# CH32V407RET-R0.net
KiCad netlist of a schematic drawn in Altium Designer
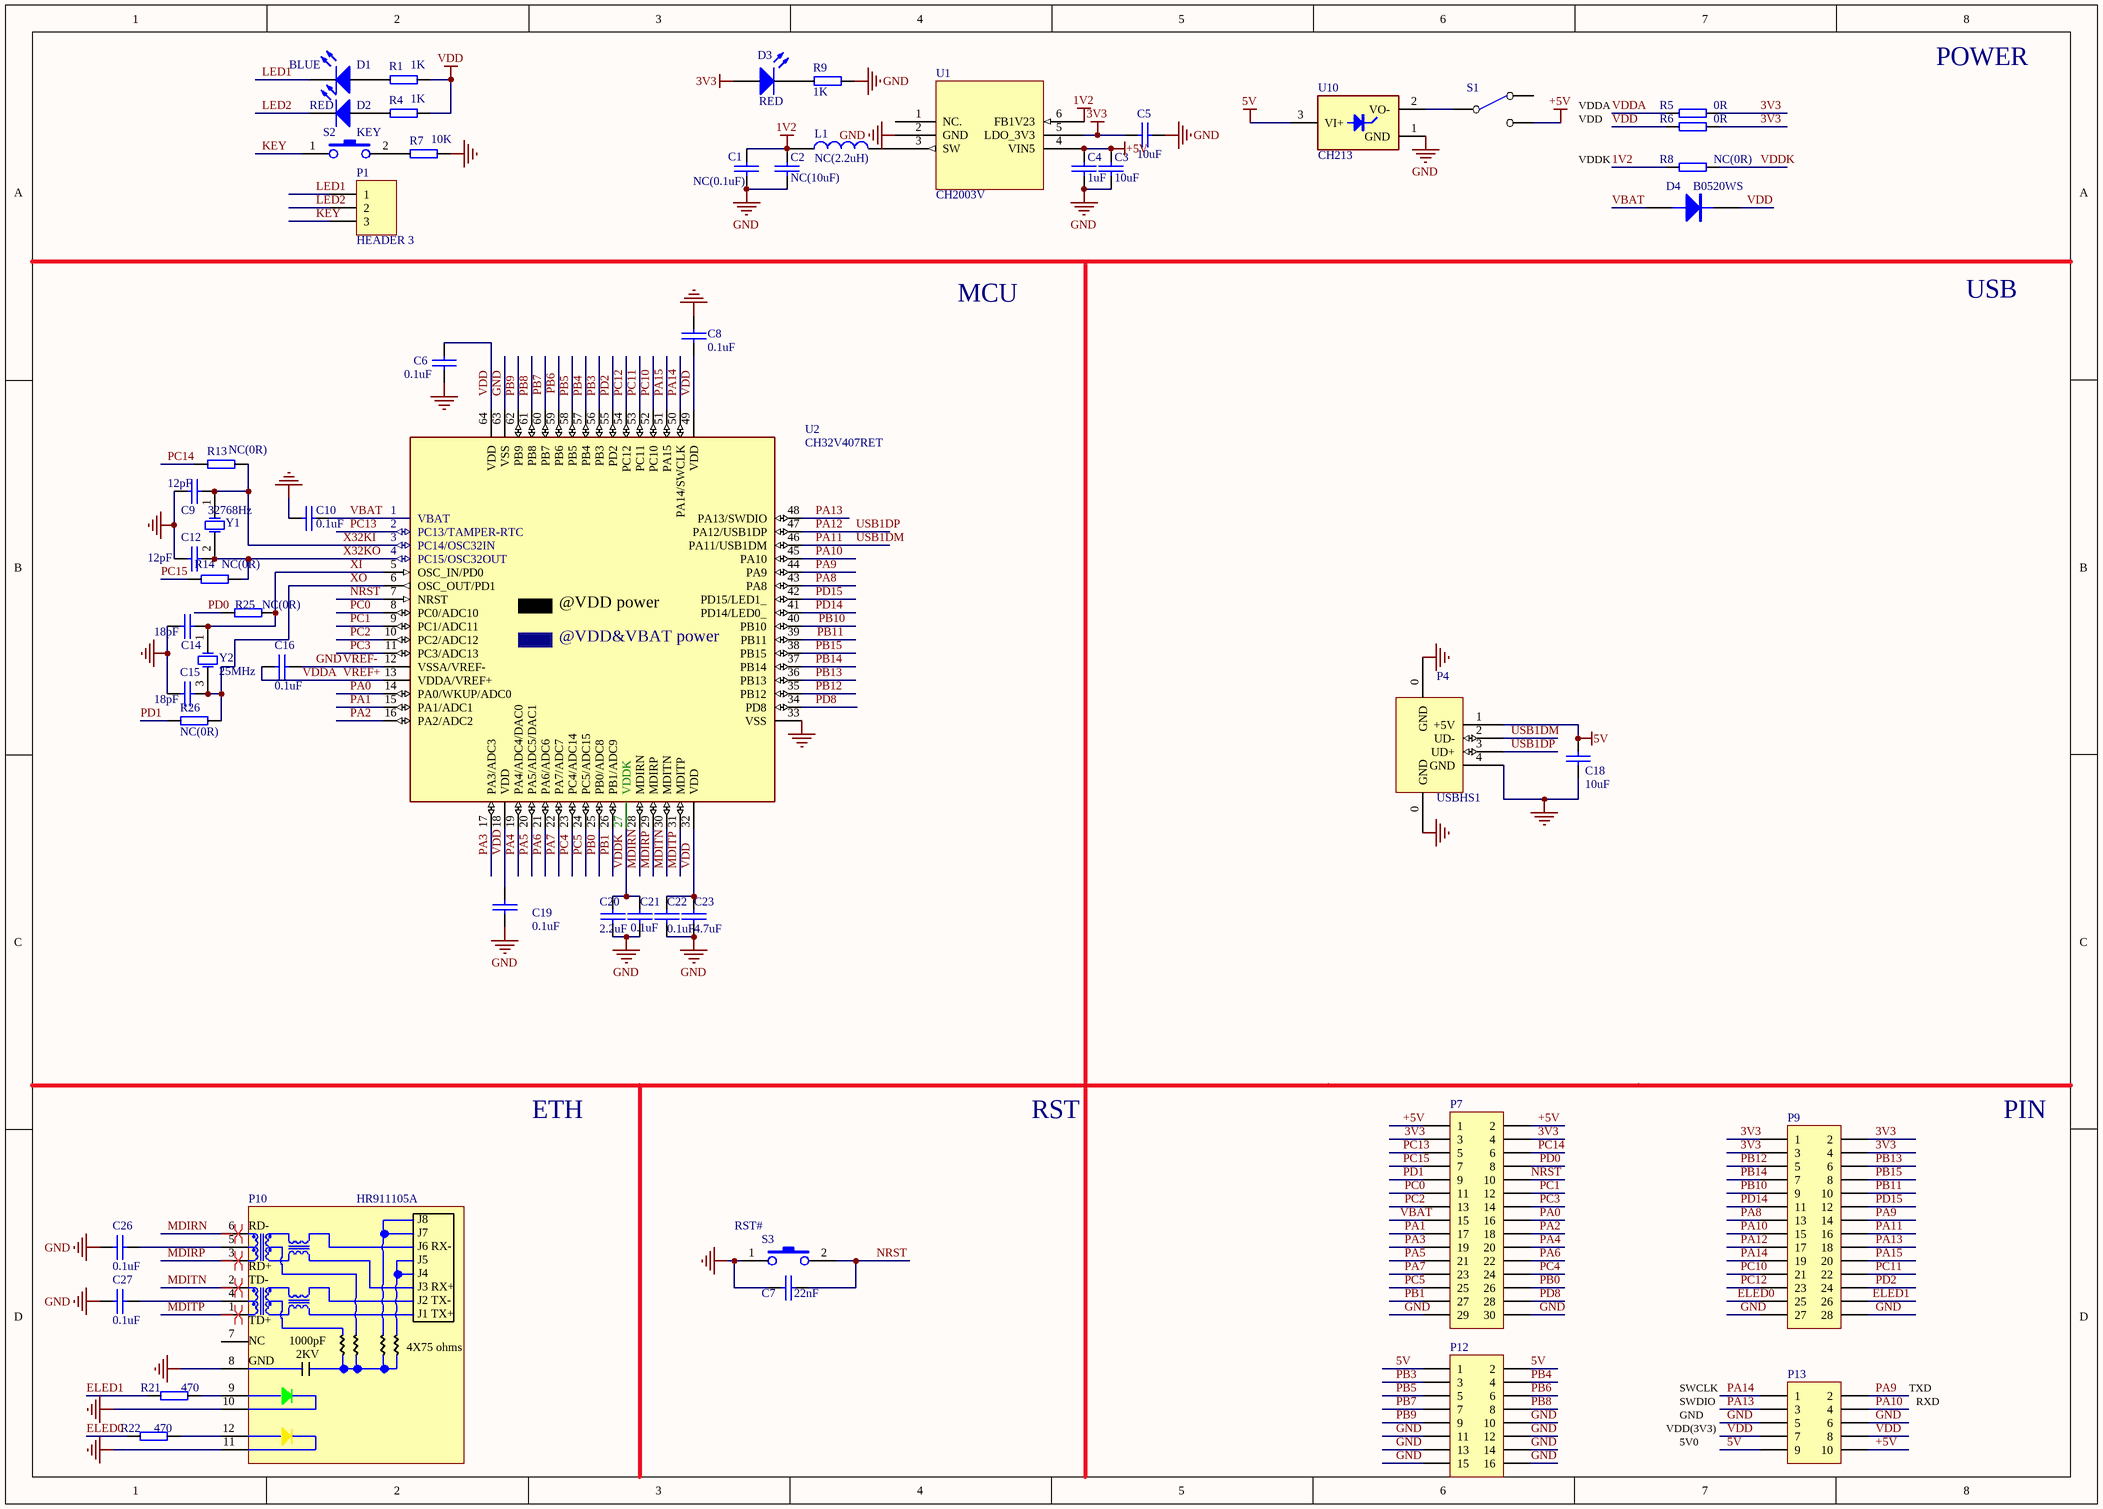
[diagram p0: CH32V407RET-R0.SchDoc]

(export (version "E")
  (design (tool "Eeschema 10.0.6"))
  (components
    (comp (ref "C1")
      (value "NC(0.1uF)")
      (footprint "0402_C")
      (description "Capacitor")
      (libsource (lib "") (part "CAP_1"))
    )
    (comp (ref "C2")
      (value "NC(10uF)")
      (footprint "0603_C")
      (description "Capacitor")
      (libsource (lib "*") (part "CAP"))
    )
    (comp (ref "C3")
      (value "10uF")
      (footprint "0603_C")
      (description "Capacitor")
      (libsource (lib "*") (part "CAP"))
    )
    (comp (ref "C4")
      (value "1uF")
      (footprint "0402_C")
      (description "Capacitor")
      (libsource (lib "") (part "CAP_1"))
    )
    (comp (ref "C5")
      (value "10uF")
      (footprint "0603_C")
      (description "Capacitor")
      (libsource (lib "*") (part "CAP"))
    )
    (comp (ref "C6")
      (value "0.1uF")
      (footprint "0402_C")
      (description "Capacitor")
      (libsource (lib "*") (part "CAP"))
    )
    (comp (ref "C7")
      (value "22nF")
      (footprint "0402_C")
      (description "Capacitor")
      (libsource (lib "") (part "CAP_2"))
    )
    (comp (ref "C8")
      (value "0.1uF")
      (footprint "0402_C")
      (description "Capacitor")
      (libsource (lib "*") (part "CAP"))
    )
    (comp (ref "C9")
      (value "12pF")
      (footprint "0402_C")
      (description "Capacitor")
      (libsource (lib "*") (part "CAP"))
    )
    (comp (ref "C10")
      (value "0.1uF")
      (footprint "0402_C")
      (description "Capacitor")
      (libsource (lib "*") (part "CAP"))
    )
    (comp (ref "C12")
      (value "12pF")
      (footprint "0402_C")
      (description "Capacitor")
      (libsource (lib "*") (part "CAP"))
    )
    (comp (ref "C14")
      (value "18pF")
      (footprint "0402_C")
      (description "Capacitor")
      (libsource (lib "*") (part "CAP"))
    )
    (comp (ref "C15")
      (value "18pF")
      (footprint "0402_C")
      (description "Capacitor")
      (libsource (lib "*") (part "CAP"))
    )
    (comp (ref "C16")
      (value "0.1uF")
      (footprint "0402_C")
      (description "Capacitor")
      (libsource (lib "*") (part "CAP"))
    )
    (comp (ref "C18")
      (value "10uF")
      (footprint "0603_C")
      (description "Capacitor")
      (libsource (lib "") (part "CAP_2"))
    )
    (comp (ref "C19")
      (value "0.1uF")
      (footprint "0402_C")
      (description "Capacitor")
      (libsource (lib "*") (part "CAP"))
    )
    (comp (ref "C20")
      (value "2.2uF")
      (footprint "0402_C")
      (description "Capacitor")
      (libsource (lib "*") (part "CAP"))
    )
    (comp (ref "C21")
      (value "0.1uF")
      (footprint "0402_C")
      (description "Capacitor")
      (libsource (lib "*") (part "CAP"))
    )
    (comp (ref "C22")
      (value "0.1uF")
      (footprint "0402_C")
      (description "Capacitor")
      (libsource (lib "*") (part "CAP"))
    )
    (comp (ref "C23")
      (value "4.7uF")
      (footprint "0402_C")
      (description "Capacitor")
      (libsource (lib "*") (part "CAP"))
    )
    (comp (ref "C26")
      (value "0.1uF")
      (footprint "0402_C")
      (description "Capacitor")
      (libsource (lib "wch_sch_others") (part "CAP"))
    )
    (comp (ref "C27")
      (value "0.1uF")
      (footprint "0402_C")
      (description "Capacitor")
      (libsource (lib "wch_sch_others") (part "CAP"))
    )
    (comp (ref "D1")
      (value "BLUE")
      (footprint "0603+")
      (description "Typical INFRARED GaAs LED")
      (fields (field (name "PUBLISHER") "Altium Limited"))
      (libsource (lib "*") (part "LED0"))
    )
    (comp (ref "D2")
      (value "RED")
      (footprint "0603+")
      (description "Typical INFRARED GaAs LED")
      (fields (field (name "PUBLISHER") "Altium Limited"))
      (libsource (lib "*") (part "LED0"))
    )
    (comp (ref "D3")
      (value "RED")
      (footprint "0603+")
      (description "Typical INFRARED GaAs LED")
      (fields (field (name "PUBLISHER") "Altium Limited"))
      (libsource (lib "*") (part "LED0"))
    )
    (comp (ref "D4")
      (value "B0520WS")
      (footprint "SOD-323")
      (description "Diode")
      (libsource (lib "*") (part "DIODE"))
    )
    (comp (ref "L1") (value "NC(2.2uH)") (footprint "CD32") (libsource (lib "*") (part "INDUCTOR")))
    (comp (ref "P1")
      (value "HEADER 3")
      (footprint "SIP3-2.54MM")
      (description "Header, 3-Pin")
      (libsource (lib "wch_sch_others") (part "HEADER 3"))
    )
    (comp (ref "P4")
      (value "USBHS1")
      (footprint "USBAF")
      (description "USB Port")
      (libsource (lib "*") (part "USB"))
    )
    (comp (ref "P7")
      (value "HEADER 15x2")
      (footprint "MYPCB:IDC30-2.54MM")
      (description "Header, 15-Pin, Dual row")
      (libsource (lib "wch_sch_others") (part "HEADER 15x2"))
    )
    (comp (ref "P9")
      (value "HEADER 14x2")
      (footprint "MYPCB:IDC28-2.54MM")
      (description "Header, 14-Pin, Dual row")
      (libsource (lib "wch_sch_others") (part "HEADER 14x2"))
    )
    (comp (ref "P10") (value "HR911105A") (footprint "HR911105A") (libsource (lib "*") (part "HR911105A")))
    (comp (ref "P12")
      (value "Ppin")
      (footprint "IDC16-2.54mm")
      (description "Header, 8-Pin, Dual row, Right Angle")
      (fields (field (name "PUBLISHER") "Altium Limited"))
      (libsource (lib "Miscellaneous Connectors") (part "Header 8X2H"))
    )
    (comp (ref "P13")
      (value "LINK")
      (footprint "IDC10-2.54mm")
      (description "Header, 5-Pin, Dual row, Right Angle")
      (fields (field (name "PUBLISHER") "Altium Limited"))
      (libsource (lib "Miscellaneous Connectors") (part "Header 5X2H"))
    )
    (comp (ref "R1") (value "1K") (footprint "0402") (libsource (lib "wch_sch_others") (part "RES")))
    (comp (ref "R4") (value "1K") (footprint "0402") (libsource (lib "wch_sch_others") (part "RES")))
    (comp (ref "R5") (value "0R") (footprint "0402") (libsource (lib "*") (part "R")))
    (comp (ref "R6") (value "0R") (footprint "0402") (libsource (lib "*") (part "R")))
    (comp (ref "R7") (value "10K") (footprint "0402") (libsource (lib "wch_sch_others") (part "RES")))
    (comp (ref "R8") (value "NC(0R)") (footprint "0402") (libsource (lib "*") (part "R")))
    (comp (ref "R9") (value "1K") (footprint "0402") (libsource (lib "wch_sch_others") (part "RES")))
    (comp (ref "R13") (value "NC(0R)") (footprint "0402") (libsource (lib "wch_sch_others") (part "RES")))
    (comp (ref "R14") (value "NC(0R)") (footprint "0402") (libsource (lib "wch_sch_others") (part "RES")))
    (comp (ref "R21") (value "470") (footprint "0402") (libsource (lib "wch_sch_others") (part "RES")))
    (comp (ref "R22") (value "470") (footprint "0402") (libsource (lib "wch_sch_others") (part "RES")))
    (comp (ref "R25") (value "NC(0R)") (footprint "0402") (libsource (lib "wch_sch_others") (part "RES")))
    (comp (ref "R26") (value "NC(0R)") (footprint "0402") (libsource (lib "wch_sch_others") (part "RES")))
    (comp (ref "S1") (value "SW SPDT") (footprint "SW1") (libsource (lib "*") (part "SW SPDT")))
    (comp (ref "S2")
      (value "KEY")
      (footprint "SMD_6.1x3.65x2.5mm-KEY")
      (libsource (lib "wch_sch_others") (part "KEY1"))
    )
    (comp (ref "S3")
      (value "RST#")
      (footprint "SMD_6.1x3.65x2.5mm-KEY")
      (libsource (lib "wch_sch_others") (part "KEY1"))
    )
    (comp (ref "U1")
      (value "CH2003V")
      (footprint "SOT-23-6")
      (description "Step-Down DC-DC Converter, 5V input, 1.23V * 800mA output, with LDO 3.3V * 200mA")
      (libsource (lib "CHXXX") (part "CH2003V"))
    )
    (comp (ref "U2")
      (value "CH32V407RET")
      (footprint "LQFP64_7X7")
      (description "RISC-V FPU HD-MCU, 175MHz, USB_480M, 100M Ethernet & Phy, CAN, ADC, DAC")
      (libsource (lib "DHXXXSCH") (part "CH32V407RET"))
    )
    (comp (ref "U10")
      (value "CH213")
      (footprint "SOT-23-3")
      (description "Ideal Diode 5V*1A")
      (libsource (lib "CHXXX") (part "CH213E"))
    )
    (comp (ref "Y1")
      (value "32768Hz")
      (footprint "FC-135")
      (description "Crystal Oscillator")
      (fields (field (name "PUBLISHER") "Altium Limited"))
      (libsource (lib "*") (part "XTAL"))
    )
    (comp (ref "Y2")
      (value "25MHz")
      (footprint "XT3225")
      (description "Crystal Oscillator")
      (fields (field (name "PUBLISHER") "Altium Limited"))
      (libsource (lib "") (part "XTAL_1"))
    )
  )
  (nets
    (net (code "1") (name "+5V") (class "Default")
      (node (ref "C3") (pin "2") (pinfunction "2_2") (pintype "passive"))
      (node (ref "C4") (pin "2") (pinfunction "2_2") (pintype "passive"))
      (node (ref "P13") (pin "10") (pinfunction "10_10") (pintype "passive"))
      (node (ref "P7") (pin "1") (pinfunction "1_1") (pintype "passive"))
      (node (ref "P7") (pin "2") (pinfunction "2_2") (pintype "passive"))
      (node (ref "S1") (pin "2") (pinfunction "NC_2") (pintype "passive"))
      (node (ref "U1") (pin "4") (pinfunction "VIN5_4") (pintype "power_in"))
    )
    (net (code "3") (name "/ELED0") (class "Default")
      (node (ref "P9") (pin "25") (pinfunction "25_25") (pintype "passive"))
      (node (ref "R22") (pin "1") (pintype "passive"))
    )
    (net (code "4") (name "/ELED1") (class "Default")
      (node (ref "P9") (pin "26") (pinfunction "26_26") (pintype "passive"))
      (node (ref "R21") (pin "1") (pintype "passive"))
    )
    (net (code "5") (name "/KEY") (class "Default")
      (node (ref "P1") (pin "3") (pinfunction "3_3") (pintype "passive"))
      (node (ref "S2") (pin "1") (pinfunction "1_1") (pintype "passive"))
    )
    (net (code "6") (name "/LED1") (class "Default")
      (node (ref "D1") (pin "2") (pinfunction "K_2") (pintype "passive"))
      (node (ref "P1") (pin "1") (pinfunction "1_1") (pintype "passive"))
    )
    (net (code "7") (name "/LED2") (class "Default")
      (node (ref "D2") (pin "2") (pinfunction "K_2") (pintype "passive"))
      (node (ref "P1") (pin "2") (pinfunction "2_2") (pintype "passive"))
    )
    (net (code "8") (name "/MDIRN") (class "Default")
      (node (ref "P10") (pin "6") (pintype "passive"))
      (node (ref "U2") (pin "28") (pinfunction "MDIRN_28") (pintype "bidirectional"))
    )
    (net (code "9") (name "/MDIRP") (class "Default")
      (node (ref "P10") (pin "3") (pintype "passive"))
      (node (ref "U2") (pin "29") (pinfunction "MDIRP_29") (pintype "bidirectional"))
    )
    (net (code "10") (name "/MDITN") (class "Default")
      (node (ref "P10") (pin "2") (pintype "passive"))
      (node (ref "U2") (pin "30") (pinfunction "MDITN_30") (pintype "bidirectional"))
    )
    (net (code "11") (name "/MDITP") (class "Default")
      (node (ref "P10") (pin "1") (pintype "passive"))
      (node (ref "U2") (pin "31") (pinfunction "MDITP_31") (pintype "bidirectional"))
    )
    (net (code "12") (name "/NRST") (class "Default")
      (node (ref "C7") (pin "2") (pinfunction "2_2") (pintype "passive"))
      (node (ref "P7") (pin "10") (pinfunction "10_10") (pintype "passive"))
      (node (ref "S3") (pin "2") (pinfunction "2_2") (pintype "passive"))
      (node (ref "U2") (pin "7") (pinfunction "NRST_7") (pintype "input"))
    )
    (net (code "13") (name "/PA0") (class "Default")
      (node (ref "P7") (pin "16") (pinfunction "16_16") (pintype "passive"))
      (node (ref "U2") (pin "14") (pinfunction "PA0/WKUP/ADC0_14") (pintype "bidirectional"))
    )
    (net (code "14") (name "/PA1") (class "Default")
      (node (ref "P7") (pin "17") (pinfunction "17_17") (pintype "passive"))
      (node (ref "U2") (pin "15") (pinfunction "PA1/ADC1_15") (pintype "bidirectional"))
    )
    (net (code "15") (name "/PA2") (class "Default")
      (node (ref "P7") (pin "18") (pinfunction "18_18") (pintype "passive"))
      (node (ref "U2") (pin "16") (pinfunction "PA2/ADC2_16") (pintype "bidirectional"))
    )
    (net (code "16") (name "/PA3") (class "Default")
      (node (ref "P7") (pin "19") (pinfunction "19_19") (pintype "passive"))
      (node (ref "U2") (pin "17") (pinfunction "PA3/ADC3_17") (pintype "bidirectional"))
    )
    (net (code "17") (name "/PA4") (class "Default")
      (node (ref "P7") (pin "20") (pinfunction "20_20") (pintype "passive"))
      (node (ref "U2") (pin "19") (pinfunction "PA4/ADC4/DAC0_19") (pintype "bidirectional"))
    )
    (net (code "18") (name "/PA5") (class "Default")
      (node (ref "P7") (pin "21") (pinfunction "21_21") (pintype "passive"))
      (node (ref "U2") (pin "20") (pinfunction "PA5/ADC5/DAC1_20") (pintype "bidirectional"))
    )
    (net (code "19") (name "/PA6") (class "Default")
      (node (ref "P7") (pin "22") (pinfunction "22_22") (pintype "passive"))
      (node (ref "U2") (pin "21") (pinfunction "PA6/ADC6_21") (pintype "bidirectional"))
    )
    (net (code "20") (name "/PA7") (class "Default")
      (node (ref "P7") (pin "23") (pinfunction "23_23") (pintype "passive"))
      (node (ref "U2") (pin "22") (pinfunction "PA7/ADC7_22") (pintype "bidirectional"))
    )
    (net (code "21") (name "/PA8") (class "Default")
      (node (ref "P9") (pin "13") (pinfunction "13_13") (pintype "passive"))
      (node (ref "U2") (pin "43") (pinfunction "PA8_43") (pintype "bidirectional"))
    )
    (net (code "22") (name "/PA9") (class "Default")
      (node (ref "P13") (pin "2") (pinfunction "2_2") (pintype "passive"))
      (node (ref "P9") (pin "14") (pinfunction "14_14") (pintype "passive"))
      (node (ref "U2") (pin "44") (pinfunction "PA9_44") (pintype "bidirectional"))
    )
    (net (code "23") (name "/PA10") (class "Default")
      (node (ref "P13") (pin "4") (pinfunction "4_4") (pintype "passive"))
      (node (ref "P9") (pin "15") (pinfunction "15_15") (pintype "passive"))
      (node (ref "U2") (pin "45") (pinfunction "PA10_45") (pintype "bidirectional"))
    )
    (net (code "24") (name "/PA11") (class "Default")
      (node (ref "P4") (pin "2") (pinfunction "UD-_2") (pintype "bidirectional"))
      (node (ref "P9") (pin "16") (pinfunction "16_16") (pintype "passive"))
      (node (ref "U2") (pin "46") (pinfunction "PA11/USB1DM_46") (pintype "bidirectional"))
    )
    (net (code "25") (name "/PA12") (class "Default")
      (node (ref "P4") (pin "3") (pinfunction "UD+_3") (pintype "bidirectional"))
      (node (ref "P9") (pin "17") (pinfunction "17_17") (pintype "passive"))
      (node (ref "U2") (pin "47") (pinfunction "PA12/USB1DP_47") (pintype "bidirectional"))
    )
    (net (code "26") (name "/PA13") (class "Default")
      (node (ref "P13") (pin "3") (pinfunction "3_3") (pintype "passive"))
      (node (ref "P9") (pin "18") (pinfunction "18_18") (pintype "passive"))
      (node (ref "U2") (pin "48") (pinfunction "PA13/SWDIO_48") (pintype "bidirectional"))
    )
    (net (code "27") (name "/PA14") (class "Default")
      (node (ref "P13") (pin "1") (pinfunction "1_1") (pintype "passive"))
      (node (ref "P9") (pin "19") (pinfunction "19_19") (pintype "passive"))
      (node (ref "U2") (pin "50") (pinfunction "PA14/SWCLK_50") (pintype "bidirectional"))
    )
    (net (code "28") (name "/PA15") (class "Default")
      (node (ref "P9") (pin "20") (pinfunction "20_20") (pintype "passive"))
      (node (ref "U2") (pin "51") (pinfunction "PA15_51") (pintype "bidirectional"))
    )
    (net (code "29") (name "/PB0") (class "Default")
      (node (ref "P7") (pin "26") (pinfunction "26_26") (pintype "passive"))
      (node (ref "U2") (pin "25") (pinfunction "PB0/ADC8_25") (pintype "bidirectional"))
    )
    (net (code "30") (name "/PB1") (class "Default")
      (node (ref "P7") (pin "27") (pinfunction "27_27") (pintype "passive"))
      (node (ref "U2") (pin "26") (pinfunction "PB1/ADC9_26") (pintype "bidirectional"))
    )
    (net (code "31") (name "/PB3") (class "Default")
      (node (ref "P12") (pin "3") (pinfunction "3_3") (pintype "passive"))
      (node (ref "U2") (pin "56") (pinfunction "PB3_56") (pintype "bidirectional"))
    )
    (net (code "32") (name "/PB4") (class "Default")
      (node (ref "P12") (pin "4") (pinfunction "4_4") (pintype "passive"))
      (node (ref "U2") (pin "57") (pinfunction "PB4_57") (pintype "bidirectional"))
    )
    (net (code "33") (name "/PB5") (class "Default")
      (node (ref "P12") (pin "5") (pinfunction "5_5") (pintype "passive"))
      (node (ref "U2") (pin "58") (pinfunction "PB5_58") (pintype "bidirectional"))
    )
    (net (code "34") (name "/PB6") (class "Default")
      (node (ref "P12") (pin "6") (pinfunction "6_6") (pintype "passive"))
      (node (ref "U2") (pin "59") (pinfunction "PB6_59") (pintype "bidirectional"))
    )
    (net (code "35") (name "/PB7") (class "Default")
      (node (ref "P12") (pin "7") (pinfunction "7_7") (pintype "passive"))
      (node (ref "U2") (pin "60") (pinfunction "PB7_60") (pintype "bidirectional"))
    )
    (net (code "36") (name "/PB8") (class "Default")
      (node (ref "P12") (pin "8") (pinfunction "8_8") (pintype "passive"))
      (node (ref "U2") (pin "61") (pinfunction "PB8_61") (pintype "bidirectional"))
    )
    (net (code "37") (name "/PB9") (class "Default")
      (node (ref "P12") (pin "9") (pinfunction "9_9") (pintype "passive"))
      (node (ref "U2") (pin "62") (pinfunction "PB9_62") (pintype "bidirectional"))
    )
    (net (code "38") (name "/PB10") (class "Default")
      (node (ref "P9") (pin "9") (pinfunction "9_9") (pintype "passive"))
      (node (ref "U2") (pin "40") (pinfunction "PB10_40") (pintype "bidirectional"))
    )
    (net (code "39") (name "/PB11") (class "Default")
      (node (ref "P9") (pin "10") (pinfunction "10_10") (pintype "passive"))
      (node (ref "U2") (pin "39") (pinfunction "PB11_39") (pintype "bidirectional"))
    )
    (net (code "40") (name "/PB12") (class "Default")
      (node (ref "P9") (pin "5") (pinfunction "5_5") (pintype "passive"))
      (node (ref "U2") (pin "35") (pinfunction "PB12_35") (pintype "bidirectional"))
    )
    (net (code "41") (name "/PB13") (class "Default")
      (node (ref "P9") (pin "6") (pinfunction "6_6") (pintype "passive"))
      (node (ref "U2") (pin "36") (pinfunction "PB13_36") (pintype "bidirectional"))
    )
    (net (code "42") (name "/PB14") (class "Default")
      (node (ref "P9") (pin "7") (pinfunction "7_7") (pintype "passive"))
      (node (ref "U2") (pin "37") (pinfunction "PB14_37") (pintype "bidirectional"))
    )
    (net (code "43") (name "/PB15") (class "Default")
      (node (ref "P9") (pin "8") (pinfunction "8_8") (pintype "passive"))
      (node (ref "U2") (pin "38") (pinfunction "PB15_38") (pintype "bidirectional"))
    )
    (net (code "44") (name "/PC0") (class "Default")
      (node (ref "P7") (pin "11") (pinfunction "11_11") (pintype "passive"))
      (node (ref "U2") (pin "8") (pinfunction "PC0/ADC10_8") (pintype "bidirectional"))
    )
    (net (code "45") (name "/PC1") (class "Default")
      (node (ref "P7") (pin "12") (pinfunction "12_12") (pintype "passive"))
      (node (ref "U2") (pin "9") (pinfunction "PC1/ADC11_9") (pintype "bidirectional"))
    )
    (net (code "46") (name "/PC2") (class "Default")
      (node (ref "P7") (pin "13") (pinfunction "13_13") (pintype "passive"))
      (node (ref "U2") (pin "10") (pinfunction "PC2/ADC12_10") (pintype "bidirectional"))
    )
    (net (code "47") (name "/PC3") (class "Default")
      (node (ref "P7") (pin "14") (pinfunction "14_14") (pintype "passive"))
      (node (ref "U2") (pin "11") (pinfunction "PC3/ADC13_11") (pintype "bidirectional"))
    )
    (net (code "48") (name "/PC4") (class "Default")
      (node (ref "P7") (pin "24") (pinfunction "24_24") (pintype "passive"))
      (node (ref "U2") (pin "23") (pinfunction "PC4/ADC14_23") (pintype "bidirectional"))
    )
    (net (code "49") (name "/PC5") (class "Default")
      (node (ref "P7") (pin "25") (pinfunction "25_25") (pintype "passive"))
      (node (ref "U2") (pin "24") (pinfunction "PC5/ADC15_24") (pintype "bidirectional"))
    )
    (net (code "50") (name "/PC10") (class "Default")
      (node (ref "P9") (pin "21") (pinfunction "21_21") (pintype "passive"))
      (node (ref "U2") (pin "52") (pinfunction "PC10_52") (pintype "bidirectional"))
    )
    (net (code "51") (name "/PC11") (class "Default")
      (node (ref "P9") (pin "22") (pinfunction "22_22") (pintype "passive"))
      (node (ref "U2") (pin "53") (pinfunction "PC11_53") (pintype "bidirectional"))
    )
    (net (code "52") (name "/PC12") (class "Default")
      (node (ref "P9") (pin "23") (pinfunction "23_23") (pintype "passive"))
      (node (ref "U2") (pin "54") (pinfunction "PC12_54") (pintype "bidirectional"))
    )
    (net (code "53") (name "/PC13") (class "Default")
      (node (ref "P7") (pin "5") (pinfunction "5_5") (pintype "passive"))
      (node (ref "U2") (pin "2") (pinfunction "PC13/TAMPER-RTC_2") (pintype "bidirectional"))
    )
    (net (code "54") (name "/PC14") (class "Default")
      (node (ref "P7") (pin "6") (pinfunction "6_6") (pintype "passive"))
      (node (ref "R13") (pin "1") (pintype "passive"))
    )
    (net (code "55") (name "/PC15") (class "Default")
      (node (ref "P7") (pin "7") (pinfunction "7_7") (pintype "passive"))
      (node (ref "R14") (pin "1") (pintype "passive"))
    )
    (net (code "56") (name "/PD0") (class "Default")
      (node (ref "P7") (pin "8") (pinfunction "8_8") (pintype "passive"))
      (node (ref "R25") (pin "1") (pintype "passive"))
    )
    (net (code "57") (name "/PD1") (class "Default")
      (node (ref "P7") (pin "9") (pinfunction "9_9") (pintype "passive"))
      (node (ref "R26") (pin "2") (pintype "passive"))
    )
    (net (code "58") (name "/PD2") (class "Default")
      (node (ref "P9") (pin "24") (pinfunction "24_24") (pintype "passive"))
      (node (ref "U2") (pin "55") (pinfunction "PD2_55") (pintype "bidirectional"))
    )
    (net (code "59") (name "/PD8") (class "Default")
      (node (ref "P7") (pin "28") (pinfunction "28_28") (pintype "passive"))
      (node (ref "U2") (pin "34") (pinfunction "PD8_34") (pintype "bidirectional"))
    )
    (net (code "60") (name "/PD14") (class "Default")
      (node (ref "P9") (pin "11") (pinfunction "11_11") (pintype "passive"))
      (node (ref "U2") (pin "41") (pinfunction "PD14/LED0__41") (pintype "bidirectional"))
    )
    (net (code "61") (name "/PD15") (class "Default")
      (node (ref "P9") (pin "12") (pinfunction "12_12") (pintype "passive"))
      (node (ref "U2") (pin "42") (pinfunction "PD15/LED1__42") (pintype "bidirectional"))
    )
    (net (code "62") (name "/VBAT") (class "Default")
      (node (ref "C10") (pin "2") (pinfunction "2_2") (pintype "passive"))
      (node (ref "D4") (pin "1") (pinfunction "A_1") (pintype "passive"))
      (node (ref "P7") (pin "15") (pinfunction "15_15") (pintype "passive"))
      (node (ref "U2") (pin "1") (pinfunction "VBAT_1") (pintype "power_in"))
    )
    (net (code "63") (name "/VDDA") (class "Default")
      (node (ref "C16") (pin "1") (pinfunction "1_1") (pintype "passive"))
      (node (ref "R5") (pin "2") (pinfunction "2_2") (pintype "passive"))
      (node (ref "U2") (pin "13") (pinfunction "VDDA/VREF+_13") (pintype "power_in"))
    )
    (net (code "64") (name "/VDDK") (class "Default")
      (node (ref "C20") (pin "2") (pinfunction "2_2") (pintype "passive"))
      (node (ref "C21") (pin "2") (pinfunction "2_2") (pintype "passive"))
      (node (ref "R8") (pin "1") (pinfunction "1_1") (pintype "passive"))
      (node (ref "U2") (pin "27") (pinfunction "VDDK_27") (pintype "power_in"))
    )
    (net (code "65") (name "/X32KI") (class "Default")
      (node (ref "C9") (pin "2") (pinfunction "2_2") (pintype "passive"))
      (node (ref "R13") (pin "2") (pintype "passive"))
      (node (ref "U2") (pin "3") (pinfunction "PC14/OSC32IN_3") (pintype "bidirectional"))
      (node (ref "Y1") (pin "1") (pinfunction "OSC1_1") (pintype "passive"))
    )
    (net (code "66") (name "/X32KO") (class "Default")
      (node (ref "C12") (pin "2") (pinfunction "2_2") (pintype "passive"))
      (node (ref "R14") (pin "2") (pintype "passive"))
      (node (ref "U2") (pin "4") (pinfunction "PC15/OSC32OUT_4") (pintype "bidirectional"))
      (node (ref "Y1") (pin "2") (pinfunction "OSC2_2") (pintype "passive"))
    )
    (net (code "67") (name "/XI") (class "Default")
      (node (ref "C14") (pin "2") (pinfunction "2_2") (pintype "passive"))
      (node (ref "R25") (pin "2") (pintype "passive"))
      (node (ref "U2") (pin "5") (pinfunction "OSC_IN/PD0_5") (pintype "input"))
      (node (ref "Y2") (pin "1") (pinfunction "OSC1_1") (pintype "passive"))
    )
    (net (code "68") (name "/XO") (class "Default")
      (node (ref "C15") (pin "2") (pinfunction "2_2") (pintype "passive"))
      (node (ref "R26") (pin "1") (pintype "passive"))
      (node (ref "U2") (pin "6") (pinfunction "OSC_OUT/PD1_6") (pintype "output"))
      (node (ref "Y2") (pin "3") (pinfunction "OSC2_3") (pintype "passive"))
    )
    (net (code "69") (name "1V2") (class "Default")
      (node (ref "C1") (pin "2") (pinfunction "2_2") (pintype "passive"))
      (node (ref "C2") (pin "2") (pinfunction "2_2") (pintype "passive"))
      (node (ref "L1") (pin "2") (pinfunction "2_2") (pintype "passive"))
      (node (ref "R8") (pin "2") (pinfunction "2_2") (pintype "passive"))
      (node (ref "U1") (pin "6") (pinfunction "FB1V23_6") (pintype "input"))
    )
    (net (code "70") (name "3V3") (class "Default")
      (node (ref "C5") (pin "2") (pinfunction "2_2") (pintype "passive"))
      (node (ref "D3") (pin "1") (pinfunction "A_1") (pintype "passive"))
      (node (ref "P7") (pin "3") (pinfunction "3_3") (pintype "passive"))
      (node (ref "P7") (pin "4") (pinfunction "4_4") (pintype "passive"))
      (node (ref "P9") (pin "1") (pinfunction "1_1") (pintype "passive"))
      (node (ref "P9") (pin "2") (pinfunction "2_2") (pintype "passive"))
      (node (ref "P9") (pin "3") (pinfunction "3_3") (pintype "passive"))
      (node (ref "P9") (pin "4") (pinfunction "4_4") (pintype "passive"))
      (node (ref "R5") (pin "1") (pinfunction "1_1") (pintype "passive"))
      (node (ref "R6") (pin "1") (pinfunction "1_1") (pintype "passive"))
      (node (ref "U1") (pin "5") (pinfunction "LDO_3V3_5") (pintype "power_in"))
    )
    (net (code "71") (name "5V") (class "Default")
      (node (ref "C18") (pin "1") (pinfunction "1_1") (pintype "passive"))
      (node (ref "P12") (pin "1") (pinfunction "1_1") (pintype "passive"))
      (node (ref "P12") (pin "2") (pinfunction "2_2") (pintype "passive"))
      (node (ref "P13") (pin "9") (pinfunction "9_9") (pintype "passive"))
      (node (ref "P4") (pin "1") (pinfunction "+5V_1") (pintype "power_in"))
      (node (ref "U10") (pin "3") (pinfunction "VI+_3") (pintype "power_in"))
    )
    (net (code "72") (name "GND") (class "Default")
      (node (ref "C1") (pin "1") (pinfunction "1_1") (pintype "passive"))
      (node (ref "C10") (pin "1") (pinfunction "1_1") (pintype "passive"))
      (node (ref "C12") (pin "1") (pinfunction "1_1") (pintype "passive"))
      (node (ref "C14") (pin "1") (pinfunction "1_1") (pintype "passive"))
      (node (ref "C15") (pin "1") (pinfunction "1_1") (pintype "passive"))
      (node (ref "C16") (pin "2") (pinfunction "2_2") (pintype "passive"))
      (node (ref "C18") (pin "2") (pinfunction "2_2") (pintype "passive"))
      (node (ref "C19") (pin "1") (pinfunction "1_1") (pintype "passive"))
      (node (ref "C2") (pin "1") (pinfunction "1_1") (pintype "passive"))
      (node (ref "C20") (pin "1") (pinfunction "1_1") (pintype "passive"))
      (node (ref "C21") (pin "1") (pinfunction "1_1") (pintype "passive"))
      (node (ref "C22") (pin "1") (pinfunction "1_1") (pintype "passive"))
      (node (ref "C23") (pin "1") (pinfunction "1_1") (pintype "passive"))
      (node (ref "C26") (pin "1") (pinfunction "1_1") (pintype "passive"))
      (node (ref "C27") (pin "1") (pinfunction "1_1") (pintype "passive"))
      (node (ref "C3") (pin "1") (pinfunction "1_1") (pintype "passive"))
      (node (ref "C4") (pin "1") (pinfunction "1_1") (pintype "passive"))
      (node (ref "C5") (pin "1") (pinfunction "1_1") (pintype "passive"))
      (node (ref "C6") (pin "1") (pinfunction "1_1") (pintype "passive"))
      (node (ref "C7") (pin "1") (pinfunction "1_1") (pintype "passive"))
      (node (ref "C8") (pin "2") (pinfunction "2_2") (pintype "passive"))
      (node (ref "C9") (pin "1") (pinfunction "1_1") (pintype "passive"))
      (node (ref "P10") (pin "10") (pintype "passive"))
      (node (ref "P10") (pin "11") (pintype "passive"))
      (node (ref "P10") (pin "8") (pintype "passive"))
      (node (ref "P12") (pin "10") (pinfunction "10_10") (pintype "passive"))
      (node (ref "P12") (pin "11") (pinfunction "11_11") (pintype "passive"))
      (node (ref "P12") (pin "12") (pinfunction "12_12") (pintype "passive"))
      (node (ref "P12") (pin "13") (pinfunction "13_13") (pintype "passive"))
      (node (ref "P12") (pin "14") (pinfunction "14_14") (pintype "passive"))
      (node (ref "P12") (pin "15") (pinfunction "15_15") (pintype "passive"))
      (node (ref "P12") (pin "16") (pinfunction "16_16") (pintype "passive"))
      (node (ref "P13") (pin "5") (pinfunction "5_5") (pintype "passive"))
      (node (ref "P13") (pin "6") (pinfunction "6_6") (pintype "passive"))
      (node (ref "P4") (pin "0") (pinfunction "GND_0") (pintype "power_in"))
      (node (ref "P4") (pin "4") (pinfunction "GND_4") (pintype "power_in"))
      (node (ref "P7") (pin "29") (pinfunction "29_29") (pintype "passive"))
      (node (ref "P7") (pin "30") (pinfunction "30_30") (pintype "passive"))
      (node (ref "P9") (pin "27") (pinfunction "27_27") (pintype "passive"))
      (node (ref "P9") (pin "28") (pinfunction "28_28") (pintype "passive"))
      (node (ref "R7") (pin "1") (pintype "passive"))
      (node (ref "R9") (pin "2") (pintype "passive"))
      (node (ref "S3") (pin "1") (pinfunction "1_1") (pintype "passive"))
      (node (ref "U1") (pin "2") (pinfunction "GND_2") (pintype "power_in"))
      (node (ref "U10") (pin "1") (pinfunction "GND_1") (pintype "power_in"))
      (node (ref "U2") (pin "12") (pinfunction "VSSA/VREF-_12") (pintype "power_in"))
      (node (ref "U2") (pin "33") (pinfunction "VSS_33") (pintype "power_in"))
      (node (ref "U2") (pin "63") (pinfunction "VSS_63") (pintype "power_in"))
    )
    (net (code "73") (name "Net-(C26-Pad2)") (class "Default")
      (node (ref "C26") (pin "2") (pinfunction "2_2") (pintype "passive"))
      (node (ref "P10") (pin "5") (pintype "passive"))
    )
    (net (code "74") (name "Net-(C27-Pad2)") (class "Default")
      (node (ref "C27") (pin "2") (pinfunction "2_2") (pintype "passive"))
      (node (ref "P10") (pin "4") (pintype "passive"))
    )
    (net (code "75") (name "Net-(D1-A)") (class "Default")
      (node (ref "D1") (pin "1") (pinfunction "A_1") (pintype "passive"))
      (node (ref "R1") (pin "2") (pintype "passive"))
    )
    (net (code "76") (name "Net-(D2-A)") (class "Default")
      (node (ref "D2") (pin "1") (pinfunction "A_1") (pintype "passive"))
      (node (ref "R4") (pin "2") (pintype "passive"))
    )
    (net (code "77") (name "Net-(D3-K)") (class "Default")
      (node (ref "D3") (pin "2") (pinfunction "K_2") (pintype "passive"))
      (node (ref "R9") (pin "1") (pintype "passive"))
    )
    (net (code "78") (name "Net-(P10-Pad9)") (class "Default")
      (node (ref "P10") (pin "9") (pintype "passive"))
      (node (ref "R21") (pin "2") (pintype "passive"))
    )
    (net (code "79") (name "Net-(P10-Pad12)") (class "Default")
      (node (ref "P10") (pin "12") (pintype "passive"))
      (node (ref "R22") (pin "2") (pintype "passive"))
    )
    (net (code "80") (name "Net-(R7-Pad2)") (class "Default")
      (node (ref "R7") (pin "2") (pintype "passive"))
      (node (ref "S2") (pin "2") (pinfunction "2_2") (pintype "passive"))
    )
    (net (code "81") (name "Net-(S1-COMMON)") (class "Default")
      (node (ref "S1") (pin "1") (pinfunction "COMMON_1") (pintype "passive"))
      (node (ref "U10") (pin "2") (pinfunction "VO-_2") (pintype "power_in"))
    )
    (net (code "82") (name "Net-(U1-SW)") (class "Default")
      (node (ref "L1") (pin "1") (pinfunction "1_1") (pintype "passive"))
      (node (ref "U1") (pin "3") (pinfunction "SW_3") (pintype "output"))
    )
    (net (code "83") (name "VDD") (class "Default")
      (node (ref "C19") (pin "2") (pinfunction "2_2") (pintype "passive"))
      (node (ref "C22") (pin "2") (pinfunction "2_2") (pintype "passive"))
      (node (ref "C23") (pin "2") (pinfunction "2_2") (pintype "passive"))
      (node (ref "C6") (pin "2") (pinfunction "2_2") (pintype "passive"))
      (node (ref "C8") (pin "1") (pinfunction "1_1") (pintype "passive"))
      (node (ref "D4") (pin "2") (pinfunction "K_2") (pintype "passive"))
      (node (ref "P13") (pin "7") (pinfunction "7_7") (pintype "passive"))
      (node (ref "P13") (pin "8") (pinfunction "8_8") (pintype "passive"))
      (node (ref "R1") (pin "1") (pintype "passive"))
      (node (ref "R4") (pin "1") (pintype "passive"))
      (node (ref "R6") (pin "2") (pinfunction "2_2") (pintype "passive"))
      (node (ref "U2") (pin "18") (pinfunction "VDD_18") (pintype "power_in"))
      (node (ref "U2") (pin "32") (pinfunction "VDD_32") (pintype "power_in"))
      (node (ref "U2") (pin "49") (pinfunction "VDD_49") (pintype "power_in"))
      (node (ref "U2") (pin "64") (pinfunction "VDD_64") (pintype "power_in"))
    )
    (net (code "84") (name "unconnected-(P10-Pad7)") (class "Default")
      (node (ref "P10") (pin "7") (pintype "passive"))
    )
    (net (code "85") (name "unconnected-(S1-NO-Pad3)") (class "Default")
      (node (ref "S1") (pin "3") (pinfunction "NO_3") (pintype "passive"))
    )
    (net (code "86") (name "unconnected-(U1-NC.-Pad1)") (class "Default")
      (node (ref "U1") (pin "1") (pinfunction "NC._1") (pintype "passive"))
    )
  )
)
